# Sensor_IBIS5.net
KiCad netlist of a schematic drawn in EAGLE
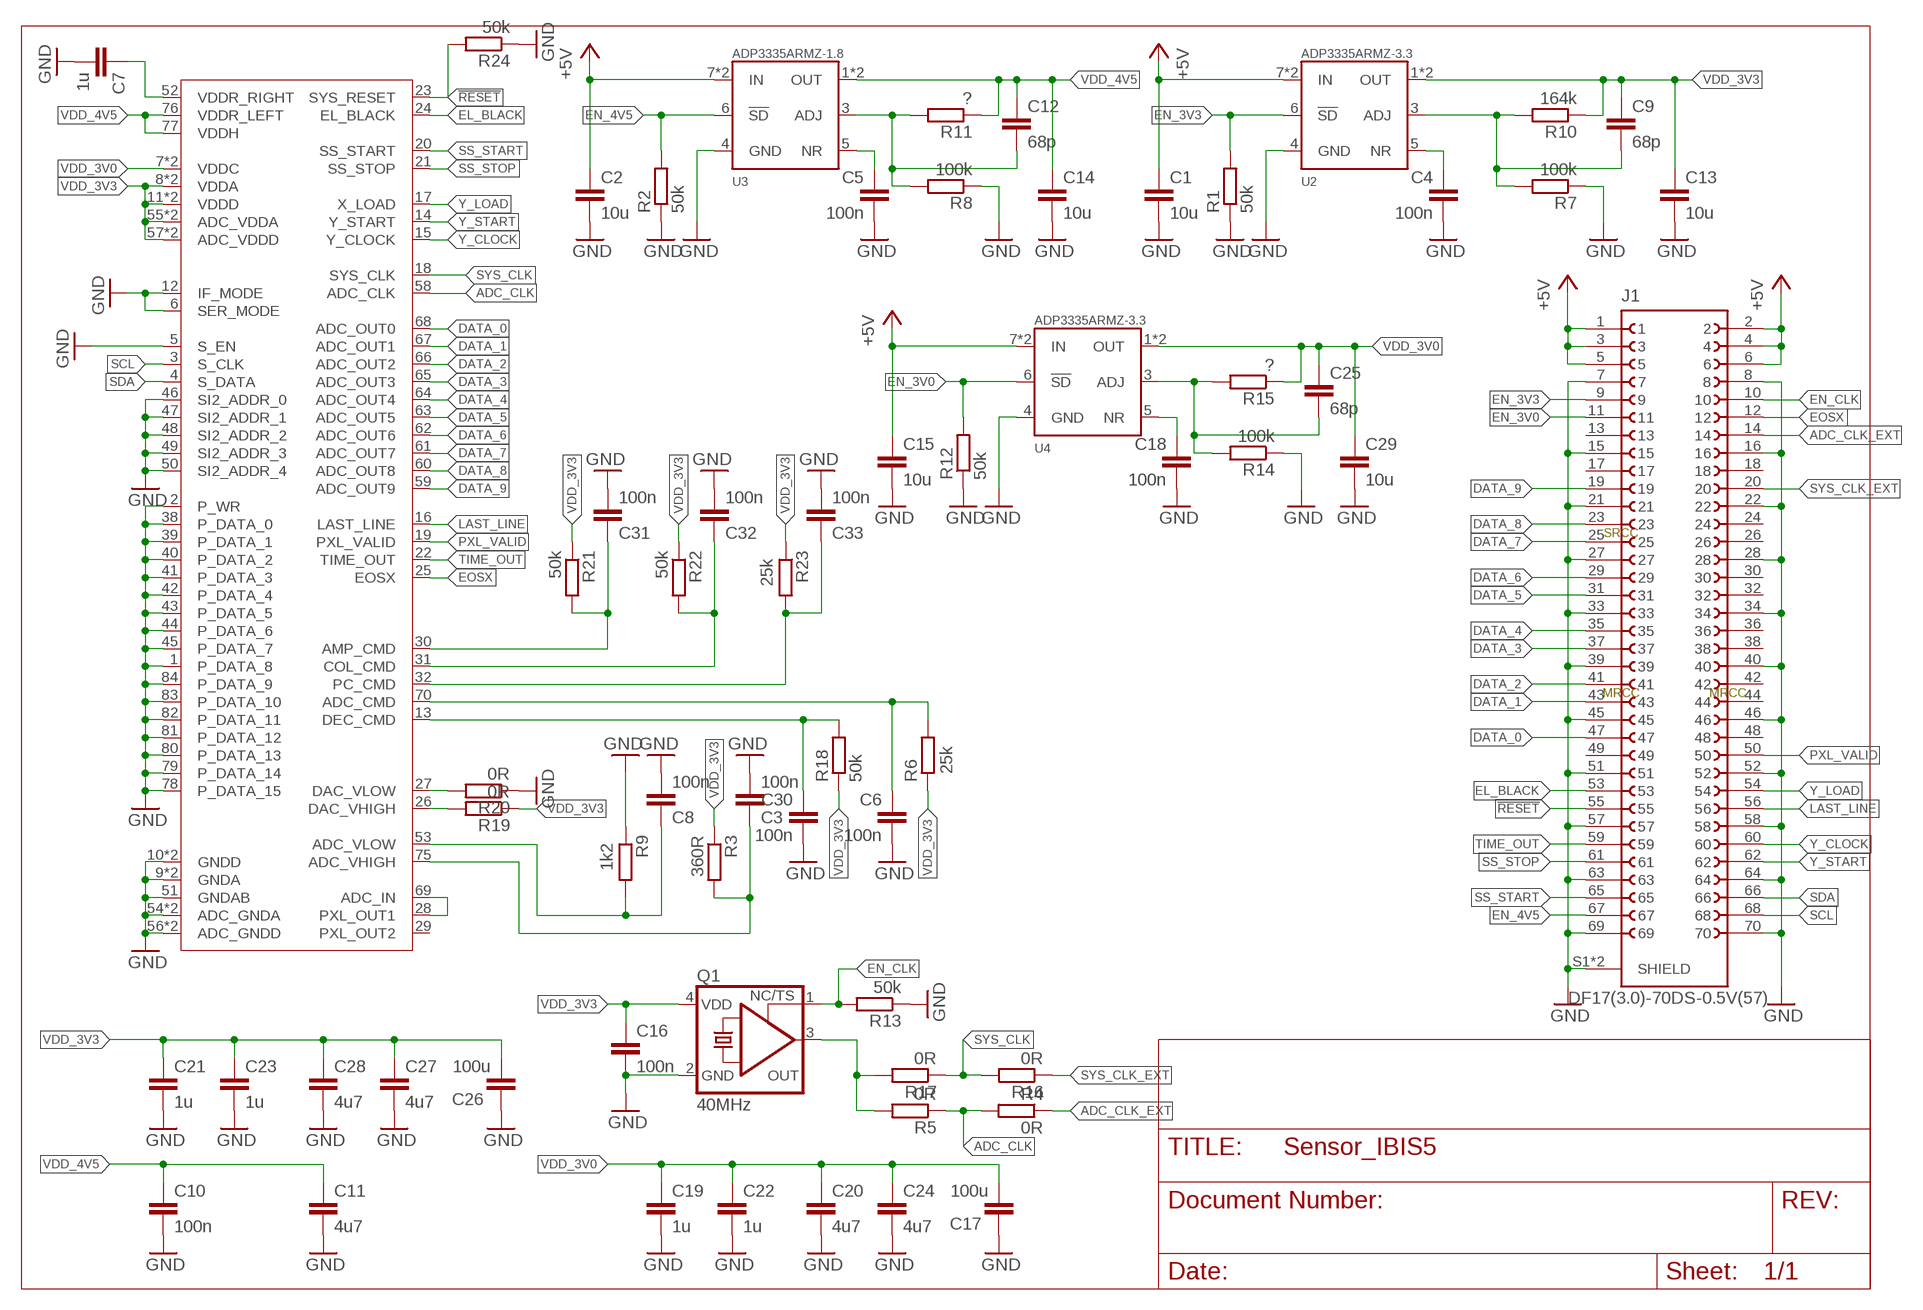
[diagram p0: schematic, sheet 1]

(export (version "E")
  (design (tool "Eeschema 10.0.6"))
  (components
    (comp (ref "C1")
      (value "10u")
      (footprint "eagle-import:C0603")
      (libsource (lib "eagle-import") (part "rcl_334_C-EUC0603"))
    )
    (comp (ref "C2")
      (value "10u")
      (footprint "eagle-import:C0603")
      (libsource (lib "eagle-import") (part "rcl_334_C-EUC0603"))
    )
    (comp (ref "C3")
      (value "100n")
      (footprint "eagle-import:C0402")
      (libsource (lib "eagle-import") (part "rcl_334_C-EUC0402"))
    )
    (comp (ref "C4")
      (value "100n")
      (footprint "eagle-import:C0402")
      (libsource (lib "eagle-import") (part "rcl_334_C-EUC0402"))
    )
    (comp (ref "C5")
      (value "100n")
      (footprint "eagle-import:C0402")
      (libsource (lib "eagle-import") (part "rcl_334_C-EUC0402"))
    )
    (comp (ref "C6")
      (value "100n")
      (footprint "eagle-import:C0402")
      (libsource (lib "eagle-import") (part "rcl_334_C-EUC0402"))
    )
    (comp (ref "C7")
      (value "1u")
      (footprint "eagle-import:C0402")
      (libsource (lib "eagle-import") (part "rcl_334_C-EUC0402"))
    )
    (comp (ref "C8")
      (value "100n")
      (footprint "eagle-import:C0402")
      (libsource (lib "eagle-import") (part "rcl_334_C-EUC0402"))
    )
    (comp (ref "C9")
      (value "68p")
      (footprint "eagle-import:C0402")
      (libsource (lib "eagle-import") (part "rcl_334_C-EUC0402"))
    )
    (comp (ref "C10")
      (value "100n")
      (footprint "eagle-import:C0402")
      (libsource (lib "eagle-import") (part "rcl_334_C-EUC0402"))
    )
    (comp (ref "C11")
      (value "4u7")
      (footprint "eagle-import:C0603")
      (libsource (lib "eagle-import") (part "rcl_334_C-EUC0603"))
    )
    (comp (ref "C12")
      (value "68p")
      (footprint "eagle-import:C0402")
      (libsource (lib "eagle-import") (part "rcl_334_C-EUC0402"))
    )
    (comp (ref "C13")
      (value "10u")
      (footprint "eagle-import:C0603")
      (libsource (lib "eagle-import") (part "rcl_334_C-EUC0603"))
    )
    (comp (ref "C14")
      (value "10u")
      (footprint "eagle-import:C0603")
      (libsource (lib "eagle-import") (part "rcl_334_C-EUC0603"))
    )
    (comp (ref "C15")
      (value "10u")
      (footprint "eagle-import:C0603")
      (libsource (lib "eagle-import") (part "rcl_334_C-EUC0603"))
    )
    (comp (ref "C16")
      (value "100n")
      (footprint "eagle-import:C0402")
      (libsource (lib "eagle-import") (part "C-EUC0402"))
    )
    (comp (ref "C17")
      (value "100u")
      (footprint "eagle-import:C1206")
      (libsource (lib "eagle-import") (part "rcl_334_C-EUC1206"))
    )
    (comp (ref "C18")
      (value "100n")
      (footprint "eagle-import:C0402")
      (libsource (lib "eagle-import") (part "rcl_334_C-EUC0402"))
    )
    (comp (ref "C19")
      (value "1u")
      (footprint "eagle-import:C0402")
      (libsource (lib "eagle-import") (part "rcl_334_C-EUC0402"))
    )
    (comp (ref "C20")
      (value "4u7")
      (footprint "eagle-import:C0603")
      (libsource (lib "eagle-import") (part "rcl_334_C-EUC0603"))
    )
    (comp (ref "C21")
      (value "1u")
      (footprint "eagle-import:C0402")
      (libsource (lib "eagle-import") (part "rcl_334_C-EUC0402"))
    )
    (comp (ref "C22")
      (value "1u")
      (footprint "eagle-import:C0402")
      (libsource (lib "eagle-import") (part "rcl_334_C-EUC0402"))
    )
    (comp (ref "C23")
      (value "1u")
      (footprint "eagle-import:C0402")
      (libsource (lib "eagle-import") (part "rcl_334_C-EUC0402"))
    )
    (comp (ref "C24")
      (value "4u7")
      (footprint "eagle-import:C0603")
      (libsource (lib "eagle-import") (part "rcl_334_C-EUC0603"))
    )
    (comp (ref "C25")
      (value "68p")
      (footprint "eagle-import:C0402")
      (libsource (lib "eagle-import") (part "rcl_334_C-EUC0402"))
    )
    (comp (ref "C26")
      (value "100u")
      (footprint "eagle-import:C1206")
      (libsource (lib "eagle-import") (part "rcl_334_C-EUC1206"))
    )
    (comp (ref "C27")
      (value "4u7")
      (footprint "eagle-import:C0603")
      (libsource (lib "eagle-import") (part "rcl_334_C-EUC0603"))
    )
    (comp (ref "C28")
      (value "4u7")
      (footprint "eagle-import:C0603")
      (libsource (lib "eagle-import") (part "rcl_334_C-EUC0603"))
    )
    (comp (ref "C29")
      (value "10u")
      (footprint "eagle-import:C0603")
      (libsource (lib "eagle-import") (part "rcl_334_C-EUC0603"))
    )
    (comp (ref "C30")
      (value "100n")
      (footprint "eagle-import:C0402")
      (libsource (lib "eagle-import") (part "rcl_334_C-EUC0402"))
    )
    (comp (ref "C31")
      (value "100n")
      (footprint "eagle-import:C0402")
      (libsource (lib "eagle-import") (part "rcl_334_C-EUC0402"))
    )
    (comp (ref "C32")
      (value "100n")
      (footprint "eagle-import:C0402")
      (libsource (lib "eagle-import") (part "rcl_334_C-EUC0402"))
    )
    (comp (ref "C33")
      (value "100n")
      (footprint "eagle-import:C0402")
      (libsource (lib "eagle-import") (part "rcl_334_C-EUC0402"))
    )
    (comp (ref "J1")
      (value "DF17(3.0)-70DS-0.5V(57)")
      (footprint "eagle-import:DF17(3.0)-70DS-0.5V(57)")
      (libsource (lib "eagle-import") (part "DF17(3.0)-70DS-0.5V(57)"))
    )
    (comp (ref "Q1")
      (value "40MHz")
      (footprint "eagle-import:3.2X2.5_KXO-V96")
      (libsource (lib "eagle-import") (part "KXO-PXO/XO-V96"))
    )
    (comp (ref "R1")
      (value "50k")
      (footprint "eagle-import:R0402")
      (libsource (lib "eagle-import") (part "R-EU_R0402"))
    )
    (comp (ref "R2")
      (value "50k")
      (footprint "eagle-import:R0402")
      (libsource (lib "eagle-import") (part "R-EU_R0402"))
    )
    (comp (ref "R3")
      (value "360R")
      (footprint "eagle-import:R0402")
      (libsource (lib "eagle-import") (part "R-EU_R0402"))
    )
    (comp (ref "R4")
      (value "0R")
      (footprint "eagle-import:R0402")
      (libsource (lib "eagle-import") (part "R-EU_R0402"))
    )
    (comp (ref "R5")
      (value "0R")
      (footprint "eagle-import:R0402")
      (libsource (lib "eagle-import") (part "R-EU_R0402"))
    )
    (comp (ref "R6")
      (value "25k")
      (footprint "eagle-import:R0402")
      (libsource (lib "eagle-import") (part "R-EU_R0402"))
    )
    (comp (ref "R7")
      (value "100k")
      (footprint "eagle-import:R0402")
      (libsource (lib "eagle-import") (part "R-EU_R0402"))
    )
    (comp (ref "R8")
      (value "100k")
      (footprint "eagle-import:R0402")
      (libsource (lib "eagle-import") (part "R-EU_R0402"))
    )
    (comp (ref "R9")
      (value "1k2")
      (footprint "eagle-import:R0402")
      (libsource (lib "eagle-import") (part "R-EU_R0402"))
    )
    (comp (ref "R10")
      (value "164k")
      (footprint "eagle-import:R0402")
      (libsource (lib "eagle-import") (part "R-EU_R0402"))
    )
    (comp (ref "R11")
      (value "?")
      (footprint "eagle-import:R0402")
      (libsource (lib "eagle-import") (part "R-EU_R0402"))
    )
    (comp (ref "R12")
      (value "50k")
      (footprint "eagle-import:R0402")
      (libsource (lib "eagle-import") (part "R-EU_R0402"))
    )
    (comp (ref "R13")
      (value "50k")
      (footprint "eagle-import:R0402")
      (libsource (lib "eagle-import") (part "R-EU_R0402"))
    )
    (comp (ref "R14")
      (value "100k")
      (footprint "eagle-import:R0402")
      (libsource (lib "eagle-import") (part "R-EU_R0402"))
    )
    (comp (ref "R15")
      (value "?")
      (footprint "eagle-import:R0402")
      (libsource (lib "eagle-import") (part "R-EU_R0402"))
    )
    (comp (ref "R16")
      (value "0R")
      (footprint "eagle-import:R0402")
      (libsource (lib "eagle-import") (part "R-EU_R0402"))
    )
    (comp (ref "R17")
      (value "0R")
      (footprint "eagle-import:R0402")
      (libsource (lib "eagle-import") (part "R-EU_R0402"))
    )
    (comp (ref "R18")
      (value "50k")
      (footprint "eagle-import:R0402")
      (libsource (lib "eagle-import") (part "R-EU_R0402"))
    )
    (comp (ref "R19")
      (value "0R")
      (footprint "eagle-import:R0402")
      (libsource (lib "eagle-import") (part "R-EU_R0402"))
    )
    (comp (ref "R20")
      (value "0R")
      (footprint "eagle-import:R0402")
      (libsource (lib "eagle-import") (part "R-EU_R0402"))
    )
    (comp (ref "R21")
      (value "50k")
      (footprint "eagle-import:R0402")
      (libsource (lib "eagle-import") (part "R-EU_R0402"))
    )
    (comp (ref "R22")
      (value "50k")
      (footprint "eagle-import:R0402")
      (libsource (lib "eagle-import") (part "R-EU_R0402"))
    )
    (comp (ref "R23")
      (value "25k")
      (footprint "eagle-import:R0402")
      (libsource (lib "eagle-import") (part "R-EU_R0402"))
    )
    (comp (ref "R24")
      (value "50k")
      (footprint "eagle-import:R0402")
      (libsource (lib "eagle-import") (part "R-EU_R0402"))
    )
    (comp (ref "U1")
      (value "CYII5FM1300AB")
      (footprint "eagle-import:LCC-84")
      (libsource (lib "eagle-import") (part "CYII5FM1300AB"))
    )
    (comp (ref "U2")
      (value "ADP3335ARMZ-3.3")
      (footprint "eagle-import:MSOP08")
      (libsource (lib "eagle-import") (part "NCP3335"))
    )
    (comp (ref "U3")
      (value "ADP3335ARMZ-1.8")
      (footprint "eagle-import:MSOP08")
      (libsource (lib "eagle-import") (part "NCP3335"))
    )
    (comp (ref "U4")
      (value "ADP3335ARMZ-3.3")
      (footprint "eagle-import:MSOP08")
      (libsource (lib "eagle-import") (part "NCP3335"))
    )
  )
  (nets
    (net (code "1") (name "+5V") (class "Default")
      (node (ref "C1") (pin "1") (pinfunction "1_1") (pintype "passive"))
      (node (ref "C15") (pin "1") (pinfunction "1_1") (pintype "passive"))
      (node (ref "C2") (pin "1") (pinfunction "1_1") (pintype "passive"))
      (node (ref "J1") (pin "1") (pinfunction "1_1") (pintype "passive"))
      (node (ref "J1") (pin "2") (pinfunction "2_2") (pintype "passive"))
      (node (ref "J1") (pin "3") (pinfunction "3_3") (pintype "passive"))
      (node (ref "J1") (pin "4") (pinfunction "4_4") (pintype "passive"))
      (node (ref "J1") (pin "5") (pinfunction "5_5") (pintype "passive"))
      (node (ref "J1") (pin "6") (pinfunction "6_6") (pintype "passive"))
      (node (ref "U2") (pin "7") (pinfunction "IN_7") (pintype "power_in"))
      (node (ref "U2") (pin "8") (pinfunction "IN_8") (pintype "power_in"))
      (node (ref "U3") (pin "7") (pinfunction "IN_7") (pintype "power_in"))
      (node (ref "U3") (pin "8") (pinfunction "IN_8") (pintype "power_in"))
      (node (ref "U4") (pin "7") (pinfunction "IN_7") (pintype "power_in"))
      (node (ref "U4") (pin "8") (pinfunction "IN_8") (pintype "power_in"))
    )
    (net (code "2") (name "/~{RESET}") (class "Default")
      (node (ref "J1") (pin "55") (pinfunction "55_55") (pintype "passive"))
      (node (ref "R24") (pin "2") (pinfunction "2_2") (pintype "passive"))
      (node (ref "U1") (pin "23") (pinfunction "SYS_RESET_23") (pintype "input"))
    )
    (net (code "3") (name "ADC_CLK") (class "Default")
      (node (ref "R4") (pin "2") (pinfunction "2_2") (pintype "passive"))
      (node (ref "R5") (pin "1") (pinfunction "1_1") (pintype "passive"))
      (node (ref "U1") (pin "58") (pinfunction "ADC_CLK_58") (pintype "input"))
    )
    (net (code "4") (name "ADC_CLK_EXT") (class "Default")
      (node (ref "J1") (pin "14") (pinfunction "14_14") (pintype "passive"))
      (node (ref "R4") (pin "1") (pinfunction "1_1") (pintype "passive"))
    )
    (net (code "5") (name "DATA_0") (class "Default")
      (node (ref "J1") (pin "47") (pinfunction "47_47") (pintype "passive"))
      (node (ref "U1") (pin "68") (pinfunction "ADC_OUT0_68") (pintype "output"))
    )
    (net (code "6") (name "DATA_1") (class "Default")
      (node (ref "J1") (pin "43") (pinfunction "43_43") (pintype "passive"))
      (node (ref "U1") (pin "67") (pinfunction "ADC_OUT1_67") (pintype "output"))
    )
    (net (code "7") (name "DATA_2") (class "Default")
      (node (ref "J1") (pin "41") (pinfunction "41_41") (pintype "passive"))
      (node (ref "U1") (pin "66") (pinfunction "ADC_OUT2_66") (pintype "output"))
    )
    (net (code "8") (name "DATA_3") (class "Default")
      (node (ref "J1") (pin "37") (pinfunction "37_37") (pintype "passive"))
      (node (ref "U1") (pin "65") (pinfunction "ADC_OUT3_65") (pintype "output"))
    )
    (net (code "9") (name "DATA_4") (class "Default")
      (node (ref "J1") (pin "35") (pinfunction "35_35") (pintype "passive"))
      (node (ref "U1") (pin "64") (pinfunction "ADC_OUT4_64") (pintype "output"))
    )
    (net (code "10") (name "DATA_5") (class "Default")
      (node (ref "J1") (pin "31") (pinfunction "31_31") (pintype "passive"))
      (node (ref "U1") (pin "63") (pinfunction "ADC_OUT5_63") (pintype "output"))
    )
    (net (code "11") (name "DATA_6") (class "Default")
      (node (ref "J1") (pin "29") (pinfunction "29_29") (pintype "passive"))
      (node (ref "U1") (pin "62") (pinfunction "ADC_OUT6_62") (pintype "output"))
    )
    (net (code "12") (name "DATA_7") (class "Default")
      (node (ref "J1") (pin "25") (pinfunction "25_25") (pintype "passive"))
      (node (ref "U1") (pin "61") (pinfunction "ADC_OUT7_61") (pintype "output"))
    )
    (net (code "13") (name "DATA_8") (class "Default")
      (node (ref "J1") (pin "23") (pinfunction "23_23") (pintype "passive"))
      (node (ref "U1") (pin "60") (pinfunction "ADC_OUT8_60") (pintype "output"))
    )
    (net (code "14") (name "DATA_9") (class "Default")
      (node (ref "J1") (pin "19") (pinfunction "19_19") (pintype "passive"))
      (node (ref "U1") (pin "59") (pinfunction "ADC_OUT9_59") (pintype "output"))
    )
    (net (code "15") (name "EL_BLACK") (class "Default")
      (node (ref "J1") (pin "53") (pinfunction "53_53") (pintype "passive"))
      (node (ref "U1") (pin "24") (pinfunction "EL_BLACK_24") (pintype "input"))
    )
    (net (code "16") (name "EN_3V0") (class "Default")
      (node (ref "J1") (pin "11") (pinfunction "11_11") (pintype "passive"))
      (node (ref "R12") (pin "2") (pinfunction "2_2") (pintype "passive"))
      (node (ref "U4") (pin "6") (pinfunction "~{SD}_6") (pintype "input"))
    )
    (net (code "17") (name "EN_3V3") (class "Default")
      (node (ref "J1") (pin "9") (pinfunction "9_9") (pintype "passive"))
      (node (ref "R1") (pin "2") (pinfunction "2_2") (pintype "passive"))
      (node (ref "U2") (pin "6") (pinfunction "~{SD}_6") (pintype "input"))
    )
    (net (code "18") (name "EN_4V5") (class "Default")
      (node (ref "J1") (pin "67") (pinfunction "67_67") (pintype "passive"))
      (node (ref "R2") (pin "2") (pinfunction "2_2") (pintype "passive"))
      (node (ref "U3") (pin "6") (pinfunction "~{SD}_6") (pintype "input"))
    )
    (net (code "19") (name "EN_CLK") (class "Default")
      (node (ref "J1") (pin "10") (pinfunction "10_10") (pintype "passive"))
      (node (ref "Q1") (pin "1") (pinfunction "TS_1") (pintype "passive"))
      (node (ref "R13") (pin "2") (pinfunction "2_2") (pintype "passive"))
    )
    (net (code "20") (name "EOSX") (class "Default")
      (node (ref "J1") (pin "12") (pinfunction "12_12") (pintype "passive"))
      (node (ref "U1") (pin "25") (pinfunction "EOSX_25") (pintype "output"))
    )
    (net (code "21") (name "GND") (class "Default")
      (node (ref "C1") (pin "2") (pinfunction "2_2") (pintype "passive"))
      (node (ref "C10") (pin "2") (pinfunction "2_2") (pintype "passive"))
      (node (ref "C11") (pin "2") (pinfunction "2_2") (pintype "passive"))
      (node (ref "C13") (pin "2") (pinfunction "2_2") (pintype "passive"))
      (node (ref "C14") (pin "2") (pinfunction "2_2") (pintype "passive"))
      (node (ref "C15") (pin "2") (pinfunction "2_2") (pintype "passive"))
      (node (ref "C16") (pin "2") (pinfunction "2_2") (pintype "passive"))
      (node (ref "C17") (pin "2") (pinfunction "2_2") (pintype "passive"))
      (node (ref "C18") (pin "2") (pinfunction "2_2") (pintype "passive"))
      (node (ref "C19") (pin "2") (pinfunction "2_2") (pintype "passive"))
      (node (ref "C2") (pin "2") (pinfunction "2_2") (pintype "passive"))
      (node (ref "C20") (pin "2") (pinfunction "2_2") (pintype "passive"))
      (node (ref "C21") (pin "2") (pinfunction "2_2") (pintype "passive"))
      (node (ref "C22") (pin "2") (pinfunction "2_2") (pintype "passive"))
      (node (ref "C23") (pin "2") (pinfunction "2_2") (pintype "passive"))
      (node (ref "C24") (pin "2") (pinfunction "2_2") (pintype "passive"))
      (node (ref "C26") (pin "2") (pinfunction "2_2") (pintype "passive"))
      (node (ref "C27") (pin "2") (pinfunction "2_2") (pintype "passive"))
      (node (ref "C28") (pin "2") (pinfunction "2_2") (pintype "passive"))
      (node (ref "C29") (pin "2") (pinfunction "2_2") (pintype "passive"))
      (node (ref "C3") (pin "2") (pinfunction "2_2") (pintype "passive"))
      (node (ref "C30") (pin "2") (pinfunction "2_2") (pintype "passive"))
      (node (ref "C31") (pin "2") (pinfunction "2_2") (pintype "passive"))
      (node (ref "C32") (pin "2") (pinfunction "2_2") (pintype "passive"))
      (node (ref "C33") (pin "2") (pinfunction "2_2") (pintype "passive"))
      (node (ref "C4") (pin "2") (pinfunction "2_2") (pintype "passive"))
      (node (ref "C5") (pin "2") (pinfunction "2_2") (pintype "passive"))
      (node (ref "C6") (pin "2") (pinfunction "2_2") (pintype "passive"))
      (node (ref "C7") (pin "2") (pinfunction "2_2") (pintype "passive"))
      (node (ref "C8") (pin "2") (pinfunction "2_2") (pintype "passive"))
      (node (ref "J1") (pin "15") (pinfunction "15_15") (pintype "passive"))
      (node (ref "J1") (pin "16") (pinfunction "16_16") (pintype "passive"))
      (node (ref "J1") (pin "21") (pinfunction "21_21") (pintype "passive"))
      (node (ref "J1") (pin "22") (pinfunction "22_22") (pintype "passive"))
      (node (ref "J1") (pin "27") (pinfunction "27_27") (pintype "passive"))
      (node (ref "J1") (pin "28") (pinfunction "28_28") (pintype "passive"))
      (node (ref "J1") (pin "33") (pinfunction "33_33") (pintype "passive"))
      (node (ref "J1") (pin "34") (pinfunction "34_34") (pintype "passive"))
      (node (ref "J1") (pin "39") (pinfunction "39_39") (pintype "passive"))
      (node (ref "J1") (pin "40") (pinfunction "40_40") (pintype "passive"))
      (node (ref "J1") (pin "45") (pinfunction "45_45") (pintype "passive"))
      (node (ref "J1") (pin "46") (pinfunction "46_46") (pintype "passive"))
      (node (ref "J1") (pin "51") (pinfunction "51_51") (pintype "passive"))
      (node (ref "J1") (pin "52") (pinfunction "52_52") (pintype "passive"))
      (node (ref "J1") (pin "57") (pinfunction "57_57") (pintype "passive"))
      (node (ref "J1") (pin "58") (pinfunction "58_58") (pintype "passive"))
      (node (ref "J1") (pin "63") (pinfunction "63_63") (pintype "passive"))
      (node (ref "J1") (pin "64") (pinfunction "64_64") (pintype "passive"))
      (node (ref "J1") (pin "69") (pinfunction "69_69") (pintype "passive"))
      (node (ref "J1") (pin "7") (pinfunction "7_7") (pintype "passive"))
      (node (ref "J1") (pin "70") (pinfunction "70_70") (pintype "passive"))
      (node (ref "J1") (pin "8") (pinfunction "8_8") (pintype "passive"))
      (node (ref "J1") (pin "S1") (pinfunction "SHIELD_S1") (pintype "passive"))
      (node (ref "J1") (pin "S2") (pinfunction "SHIELD_S2") (pintype "passive"))
      (node (ref "Q1") (pin "2") (pinfunction "GND_2") (pintype "power_in"))
      (node (ref "R1") (pin "1") (pinfunction "1_1") (pintype "passive"))
      (node (ref "R12") (pin "1") (pinfunction "1_1") (pintype "passive"))
      (node (ref "R13") (pin "1") (pinfunction "1_1") (pintype "passive"))
      (node (ref "R14") (pin "1") (pinfunction "1_1") (pintype "passive"))
      (node (ref "R2") (pin "1") (pinfunction "1_1") (pintype "passive"))
      (node (ref "R20") (pin "1") (pinfunction "1_1") (pintype "passive"))
      (node (ref "R24") (pin "1") (pinfunction "1_1") (pintype "passive"))
      (node (ref "R7") (pin "1") (pinfunction "1_1") (pintype "passive"))
      (node (ref "R8") (pin "1") (pinfunction "1_1") (pintype "passive"))
      (node (ref "R9") (pin "1") (pinfunction "1_1") (pintype "passive"))
      (node (ref "U1") (pin "1") (pinfunction "P_DATA_8_1") (pintype "input"))
      (node (ref "U1") (pin "10") (pinfunction "GNDD_10") (pintype "passive"))
      (node (ref "U1") (pin "12") (pinfunction "IF_MODE_12") (pintype "input"))
      (node (ref "U1") (pin "2") (pinfunction "P_WR_2") (pintype "input"))
      (node (ref "U1") (pin "34") (pinfunction "GNDD_34") (pintype "passive"))
      (node (ref "U1") (pin "35") (pinfunction "GNDA_35") (pintype "passive"))
      (node (ref "U1") (pin "38") (pinfunction "P_DATA_0_38") (pintype "input"))
      (node (ref "U1") (pin "39") (pinfunction "P_DATA_1_39") (pintype "input"))
      (node (ref "U1") (pin "40") (pinfunction "P_DATA_2_40") (pintype "input"))
      (node (ref "U1") (pin "41") (pinfunction "P_DATA_3_41") (pintype "input"))
      (node (ref "U1") (pin "42") (pinfunction "P_DATA_4_42") (pintype "input"))
      (node (ref "U1") (pin "43") (pinfunction "P_DATA_5_43") (pintype "input"))
      (node (ref "U1") (pin "44") (pinfunction "P_DATA_6_44") (pintype "input"))
      (node (ref "U1") (pin "45") (pinfunction "P_DATA_7_45") (pintype "input"))
      (node (ref "U1") (pin "46") (pinfunction "SI2_ADDR_0_46") (pintype "input"))
      (node (ref "U1") (pin "47") (pinfunction "SI2_ADDR_1_47") (pintype "input"))
      (node (ref "U1") (pin "48") (pinfunction "SI2_ADDR_2_48") (pintype "input"))
      (node (ref "U1") (pin "49") (pinfunction "SI2_ADDR_3_49") (pintype "input"))
      (node (ref "U1") (pin "5") (pinfunction "S_EN_5") (pintype "input"))
      (node (ref "U1") (pin "50") (pinfunction "SI2_ADDR_4_50") (pintype "input"))
      (node (ref "U1") (pin "51") (pinfunction "GNDAB_51") (pintype "passive"))
      (node (ref "U1") (pin "54") (pinfunction "ADC_GNDA_54") (pintype "passive"))
      (node (ref "U1") (pin "56") (pinfunction "ADC_GNDD_56") (pintype "passive"))
      (node (ref "U1") (pin "6") (pinfunction "SER_MODE_6") (pintype "input"))
      (node (ref "U1") (pin "72") (pinfunction "ADC_GNDA_72") (pintype "passive"))
      (node (ref "U1") (pin "73") (pinfunction "ADC_GNDD_73") (pintype "passive"))
      (node (ref "U1") (pin "78") (pinfunction "P_DATA_15_78") (pintype "input"))
      (node (ref "U1") (pin "79") (pinfunction "P_DATA_14_79") (pintype "input"))
      (node (ref "U1") (pin "80") (pinfunction "P_DATA_13_80") (pintype "input"))
      (node (ref "U1") (pin "81") (pinfunction "P_DATA_12_81") (pintype "input"))
      (node (ref "U1") (pin "82") (pinfunction "P_DATA_11_82") (pintype "input"))
      (node (ref "U1") (pin "83") (pinfunction "P_DATA_10_83") (pintype "input"))
      (node (ref "U1") (pin "84") (pinfunction "P_DATA_9_84") (pintype "input"))
      (node (ref "U1") (pin "9") (pinfunction "GNDA_9") (pintype "passive"))
      (node (ref "U2") (pin "4") (pinfunction "GND_4") (pintype "power_in"))
      (node (ref "U3") (pin "4") (pinfunction "GND_4") (pintype "power_in"))
      (node (ref "U4") (pin "4") (pinfunction "GND_4") (pintype "power_in"))
    )
    (net (code "22") (name "LAST_LINE") (class "Default")
      (node (ref "J1") (pin "56") (pinfunction "56_56") (pintype "passive"))
      (node (ref "U1") (pin "16") (pinfunction "LAST_LINE_16") (pintype "output"))
    )
    (net (code "23") (name "Net-(Q1-OUT)") (class "Default")
      (node (ref "Q1") (pin "3") (pinfunction "OUT_3") (pintype "output"))
      (node (ref "R17") (pin "2") (pinfunction "2_2") (pintype "passive"))
      (node (ref "R5") (pin "2") (pinfunction "2_2") (pintype "passive"))
    )
    (net (code "24") (name "Net-(U1-ADC_CMD)") (class "Default")
      (node (ref "C6") (pin "1") (pinfunction "1_1") (pintype "passive"))
      (node (ref "R6") (pin "2") (pinfunction "2_2") (pintype "passive"))
      (node (ref "U1") (pin "70") (pinfunction "ADC_CMD_70") (pintype "input"))
    )
    (net (code "25") (name "Net-(U1-ADC_IN)") (class "Default")
      (node (ref "U1") (pin "28") (pinfunction "PXL_OUT1_28") (pintype "output"))
      (node (ref "U1") (pin "69") (pinfunction "ADC_IN_69") (pintype "input"))
    )
    (net (code "26") (name "Net-(U1-ADC_VHIGH)") (class "Default")
      (node (ref "C3") (pin "1") (pinfunction "1_1") (pintype "passive"))
      (node (ref "R3") (pin "2") (pinfunction "2_2") (pintype "passive"))
      (node (ref "U1") (pin "75") (pinfunction "ADC_VHIGH_75") (pintype "input"))
    )
    (net (code "27") (name "Net-(U1-ADC_VLOW)") (class "Default")
      (node (ref "C8") (pin "1") (pinfunction "1_1") (pintype "passive"))
      (node (ref "R9") (pin "2") (pinfunction "2_2") (pintype "passive"))
      (node (ref "U1") (pin "53") (pinfunction "ADC_VLOW_53") (pintype "input"))
    )
    (net (code "28") (name "Net-(U1-AMP_CMD)") (class "Default")
      (node (ref "C31") (pin "1") (pinfunction "1_1") (pintype "passive"))
      (node (ref "R21") (pin "2") (pinfunction "2_2") (pintype "passive"))
      (node (ref "U1") (pin "30") (pinfunction "AMP_CMD_30") (pintype "input"))
    )
    (net (code "29") (name "Net-(U1-COL_CMD)") (class "Default")
      (node (ref "C32") (pin "1") (pinfunction "1_1") (pintype "passive"))
      (node (ref "R22") (pin "2") (pinfunction "2_2") (pintype "passive"))
      (node (ref "U1") (pin "31") (pinfunction "COL_CMD_31") (pintype "input"))
    )
    (net (code "30") (name "Net-(U1-DAC_VHIGH)") (class "Default")
      (node (ref "R19") (pin "2") (pinfunction "2_2") (pintype "passive"))
      (node (ref "U1") (pin "26") (pinfunction "DAC_VHIGH_26") (pintype "input"))
    )
    (net (code "31") (name "Net-(U1-DAC_VLOW)") (class "Default")
      (node (ref "R20") (pin "2") (pinfunction "2_2") (pintype "passive"))
      (node (ref "U1") (pin "27") (pinfunction "DAC_VLOW_27") (pintype "input"))
    )
    (net (code "32") (name "Net-(U1-DEC_CMD)") (class "Default")
      (node (ref "C30") (pin "1") (pinfunction "1_1") (pintype "passive"))
      (node (ref "R18") (pin "2") (pinfunction "2_2") (pintype "passive"))
      (node (ref "U1") (pin "13") (pinfunction "DEC_CMD_13") (pintype "input"))
    )
    (net (code "33") (name "Net-(U1-PC_CMD)") (class "Default")
      (node (ref "C33") (pin "1") (pinfunction "1_1") (pintype "passive"))
      (node (ref "R23") (pin "2") (pinfunction "2_2") (pintype "passive"))
      (node (ref "U1") (pin "32") (pinfunction "PC_CMD_32") (pintype "input"))
    )
    (net (code "34") (name "Net-(U1-VDDR_RIGHT)") (class "Default")
      (node (ref "C7") (pin "1") (pinfunction "1_1") (pintype "passive"))
      (node (ref "U1") (pin "52") (pinfunction "VDDR_RIGHT_52") (pintype "power_in"))
    )
    (net (code "35") (name "Net-(U2-ADJ)") (class "Default")
      (node (ref "C9") (pin "2") (pinfunction "2_2") (pintype "passive"))
      (node (ref "R10") (pin "2") (pinfunction "2_2") (pintype "passive"))
      (node (ref "R7") (pin "2") (pinfunction "2_2") (pintype "passive"))
      (node (ref "U2") (pin "3") (pinfunction "ADJ_3") (pintype "passive"))
    )
    (net (code "36") (name "Net-(U2-NR)") (class "Default")
      (node (ref "C4") (pin "1") (pinfunction "1_1") (pintype "passive"))
      (node (ref "U2") (pin "5") (pinfunction "NR_5") (pintype "passive"))
    )
    (net (code "37") (name "Net-(U3-ADJ)") (class "Default")
      (node (ref "C12") (pin "2") (pinfunction "2_2") (pintype "passive"))
      (node (ref "R11") (pin "2") (pinfunction "2_2") (pintype "passive"))
      (node (ref "R8") (pin "2") (pinfunction "2_2") (pintype "passive"))
      (node (ref "U3") (pin "3") (pinfunction "ADJ_3") (pintype "passive"))
    )
    (net (code "38") (name "Net-(U3-NR)") (class "Default")
      (node (ref "C5") (pin "1") (pinfunction "1_1") (pintype "passive"))
      (node (ref "U3") (pin "5") (pinfunction "NR_5") (pintype "passive"))
    )
    (net (code "39") (name "Net-(U4-ADJ)") (class "Default")
      (node (ref "C25") (pin "2") (pinfunction "2_2") (pintype "passive"))
      (node (ref "R14") (pin "2") (pinfunction "2_2") (pintype "passive"))
      (node (ref "R15") (pin "2") (pinfunction "2_2") (pintype "passive"))
      (node (ref "U4") (pin "3") (pinfunction "ADJ_3") (pintype "passive"))
    )
    (net (code "40") (name "Net-(U4-NR)") (class "Default")
      (node (ref "C18") (pin "1") (pinfunction "1_1") (pintype "passive"))
      (node (ref "U4") (pin "5") (pinfunction "NR_5") (pintype "passive"))
    )
    (net (code "41") (name "PXL_VALID") (class "Default")
      (node (ref "J1") (pin "50") (pinfunction "50_50") (pintype "passive"))
      (node (ref "U1") (pin "19") (pinfunction "PXL_VALID_19") (pintype "output"))
    )
    (net (code "42") (name "SCL") (class "Default")
      (node (ref "J1") (pin "68") (pinfunction "68_68") (pintype "passive"))
      (node (ref "U1") (pin "3") (pinfunction "S_CLK_3") (pintype "input"))
    )
    (net (code "43") (name "SDA") (class "Default")
      (node (ref "J1") (pin "66") (pinfunction "66_66") (pintype "passive"))
      (node (ref "U1") (pin "4") (pinfunction "S_DATA_4") (pintype "input"))
    )
    (net (code "44") (name "SS_START") (class "Default")
      (node (ref "J1") (pin "65") (pinfunction "65_65") (pintype "passive"))
      (node (ref "U1") (pin "20") (pinfunction "SS_START_20") (pintype "input"))
    )
    (net (code "45") (name "SS_STOP") (class "Default")
      (node (ref "J1") (pin "61") (pinfunction "61_61") (pintype "passive"))
      (node (ref "U1") (pin "21") (pinfunction "SS_STOP_21") (pintype "input"))
    )
    (net (code "46") (name "SYS_CLK") (class "Default")
      (node (ref "R16") (pin "2") (pinfunction "2_2") (pintype "passive"))
      (node (ref "R17") (pin "1") (pinfunction "1_1") (pintype "passive"))
      (node (ref "U1") (pin "18") (pinfunction "SYS_CLK_18") (pintype "input"))
    )
    (net (code "47") (name "SYS_CLK_EXT") (class "Default")
      (node (ref "J1") (pin "20") (pinfunction "20_20") (pintype "passive"))
      (node (ref "R16") (pin "1") (pinfunction "1_1") (pintype "passive"))
    )
    (net (code "48") (name "TIME_OUT") (class "Default")
      (node (ref "J1") (pin "59") (pinfunction "59_59") (pintype "passive"))
      (node (ref "U1") (pin "22") (pinfunction "TIME_OUT_22") (pintype "output"))
    )
    (net (code "49") (name "VDD_3V0") (class "Default")
      (node (ref "C17") (pin "1") (pinfunction "1_1") (pintype "passive"))
      (node (ref "C19") (pin "1") (pinfunction "1_1") (pintype "passive"))
      (node (ref "C20") (pin "1") (pinfunction "1_1") (pintype "passive"))
      (node (ref "C22") (pin "1") (pinfunction "1_1") (pintype "passive"))
      (node (ref "C24") (pin "1") (pinfunction "1_1") (pintype "passive"))
      (node (ref "C25") (pin "1") (pinfunction "1_1") (pintype "passive"))
      (node (ref "C29") (pin "1") (pinfunction "1_1") (pintype "passive"))
      (node (ref "R15") (pin "1") (pinfunction "1_1") (pintype "passive"))
      (node (ref "U1") (pin "37") (pinfunction "VDDC_37") (pintype "power_in"))
      (node (ref "U1") (pin "7") (pinfunction "VDDC_7") (pintype "power_in"))
      (node (ref "U4") (pin "1") (pinfunction "OUT_1") (pintype "power_in"))
      (node (ref "U4") (pin "2") (pinfunction "OUT_2") (pintype "power_in"))
    )
    (net (code "50") (name "VDD_3V3") (class "Default")
      (node (ref "C13") (pin "1") (pinfunction "1_1") (pintype "passive"))
      (node (ref "C16") (pin "1") (pinfunction "1_1") (pintype "passive"))
      (node (ref "C21") (pin "1") (pinfunction "1_1") (pintype "passive"))
      (node (ref "C23") (pin "1") (pinfunction "1_1") (pintype "passive"))
      (node (ref "C26") (pin "1") (pinfunction "1_1") (pintype "passive"))
      (node (ref "C27") (pin "1") (pinfunction "1_1") (pintype "passive"))
      (node (ref "C28") (pin "1") (pinfunction "1_1") (pintype "passive"))
      (node (ref "C9") (pin "1") (pinfunction "1_1") (pintype "passive"))
      (node (ref "Q1") (pin "4") (pinfunction "VDD_4") (pintype "power_in"))
      (node (ref "R10") (pin "1") (pinfunction "1_1") (pintype "passive"))
      (node (ref "R18") (pin "1") (pinfunction "1_1") (pintype "passive"))
      (node (ref "R19") (pin "1") (pinfunction "1_1") (pintype "passive"))
      (node (ref "R21") (pin "1") (pinfunction "1_1") (pintype "passive"))
      (node (ref "R22") (pin "1") (pinfunction "1_1") (pintype "passive"))
      (node (ref "R23") (pin "1") (pinfunction "1_1") (pintype "passive"))
      (node (ref "R3") (pin "1") (pinfunction "1_1") (pintype "passive"))
      (node (ref "R6") (pin "1") (pinfunction "1_1") (pintype "passive"))
      (node (ref "U1") (pin "11") (pinfunction "VDDD_11") (pintype "power_in"))
      (node (ref "U1") (pin "33") (pinfunction "VDDD_33") (pintype "power_in"))
      (node (ref "U1") (pin "36") (pinfunction "VDDA_36") (pintype "power_in"))
      (node (ref "U1") (pin "55") (pinfunction "ADC_VDDA_55") (pintype "power_in"))
      (node (ref "U1") (pin "57") (pinfunction "ADC_VDDD_57") (pintype "power_in"))
      (node (ref "U1") (pin "71") (pinfunction "ADC_VDDD_71") (pintype "power_in"))
      (node (ref "U1") (pin "74") (pinfunction "ADC_VDDA_74") (pintype "power_in"))
      (node (ref "U1") (pin "8") (pinfunction "VDDA_8") (pintype "power_in"))
      (node (ref "U2") (pin "1") (pinfunction "OUT_1") (pintype "power_in"))
      (node (ref "U2") (pin "2") (pinfunction "OUT_2") (pintype "power_in"))
    )
    (net (code "51") (name "VDD_4V5") (class "Default")
      (node (ref "C10") (pin "1") (pinfunction "1_1") (pintype "passive"))
      (node (ref "C11") (pin "1") (pinfunction "1_1") (pintype "passive"))
      (node (ref "C12") (pin "1") (pinfunction "1_1") (pintype "passive"))
      (node (ref "C14") (pin "1") (pinfunction "1_1") (pintype "passive"))
      (node (ref "R11") (pin "1") (pinfunction "1_1") (pintype "passive"))
      (node (ref "U1") (pin "76") (pinfunction "VDDR_LEFT_76") (pintype "power_in"))
      (node (ref "U1") (pin "77") (pinfunction "VDDH_77") (pintype "power_in"))
      (node (ref "U3") (pin "1") (pinfunction "OUT_1") (pintype "power_in"))
      (node (ref "U3") (pin "2") (pinfunction "OUT_2") (pintype "power_in"))
    )
    (net (code "52") (name "Y_CLOCK") (class "Default")
      (node (ref "J1") (pin "60") (pinfunction "60_60") (pintype "passive"))
      (node (ref "U1") (pin "15") (pinfunction "Y_CLOCK_15") (pintype "input"))
    )
    (net (code "53") (name "Y_LOAD") (class "Default")
      (node (ref "J1") (pin "54") (pinfunction "54_54") (pintype "passive"))
      (node (ref "U1") (pin "17") (pinfunction "X_LOAD_17") (pintype "input"))
    )
    (net (code "54") (name "Y_START") (class "Default")
      (node (ref "J1") (pin "62") (pinfunction "62_62") (pintype "passive"))
      (node (ref "U1") (pin "14") (pinfunction "Y_START_14") (pintype "input"))
    )
    (net (code "55") (name "unconnected-(J1-Pad13)") (class "Default")
      (node (ref "J1") (pin "13") (pinfunction "13_13") (pintype "passive"))
    )
    (net (code "56") (name "unconnected-(J1-Pad17)") (class "Default")
      (node (ref "J1") (pin "17") (pinfunction "17_17") (pintype "passive"))
    )
    (net (code "57") (name "unconnected-(J1-Pad18)") (class "Default")
      (node (ref "J1") (pin "18") (pinfunction "18_18") (pintype "passive"))
    )
    (net (code "58") (name "unconnected-(J1-Pad24)") (class "Default")
      (node (ref "J1") (pin "24") (pinfunction "24_24") (pintype "passive"))
    )
    (net (code "59") (name "unconnected-(J1-Pad26)") (class "Default")
      (node (ref "J1") (pin "26") (pinfunction "26_26") (pintype "passive"))
    )
    (net (code "60") (name "unconnected-(J1-Pad30)") (class "Default")
      (node (ref "J1") (pin "30") (pinfunction "30_30") (pintype "passive"))
    )
    (net (code "61") (name "unconnected-(J1-Pad32)") (class "Default")
      (node (ref "J1") (pin "32") (pinfunction "32_32") (pintype "passive"))
    )
    (net (code "62") (name "unconnected-(J1-Pad36)") (class "Default")
      (node (ref "J1") (pin "36") (pinfunction "36_36") (pintype "passive"))
    )
    (net (code "63") (name "unconnected-(J1-Pad38)") (class "Default")
      (node (ref "J1") (pin "38") (pinfunction "38_38") (pintype "passive"))
    )
    (net (code "64") (name "unconnected-(J1-Pad42)") (class "Default")
      (node (ref "J1") (pin "42") (pinfunction "42_42") (pintype "passive"))
    )
    (net (code "65") (name "unconnected-(J1-Pad44)") (class "Default")
      (node (ref "J1") (pin "44") (pinfunction "44_44") (pintype "passive"))
    )
    (net (code "66") (name "unconnected-(J1-Pad48)") (class "Default")
      (node (ref "J1") (pin "48") (pinfunction "48_48") (pintype "passive"))
    )
    (net (code "67") (name "unconnected-(J1-Pad49)") (class "Default")
      (node (ref "J1") (pin "49") (pinfunction "49_49") (pintype "passive"))
    )
    (net (code "68") (name "unconnected-(U1-PXL_OUT2-Pad29)") (class "Default")
      (node (ref "U1") (pin "29") (pinfunction "PXL_OUT2_29") (pintype "output"))
    )
  )
)
